# 05_-_USB.net
KiCad netlist of a schematic drawn in Altium Designer
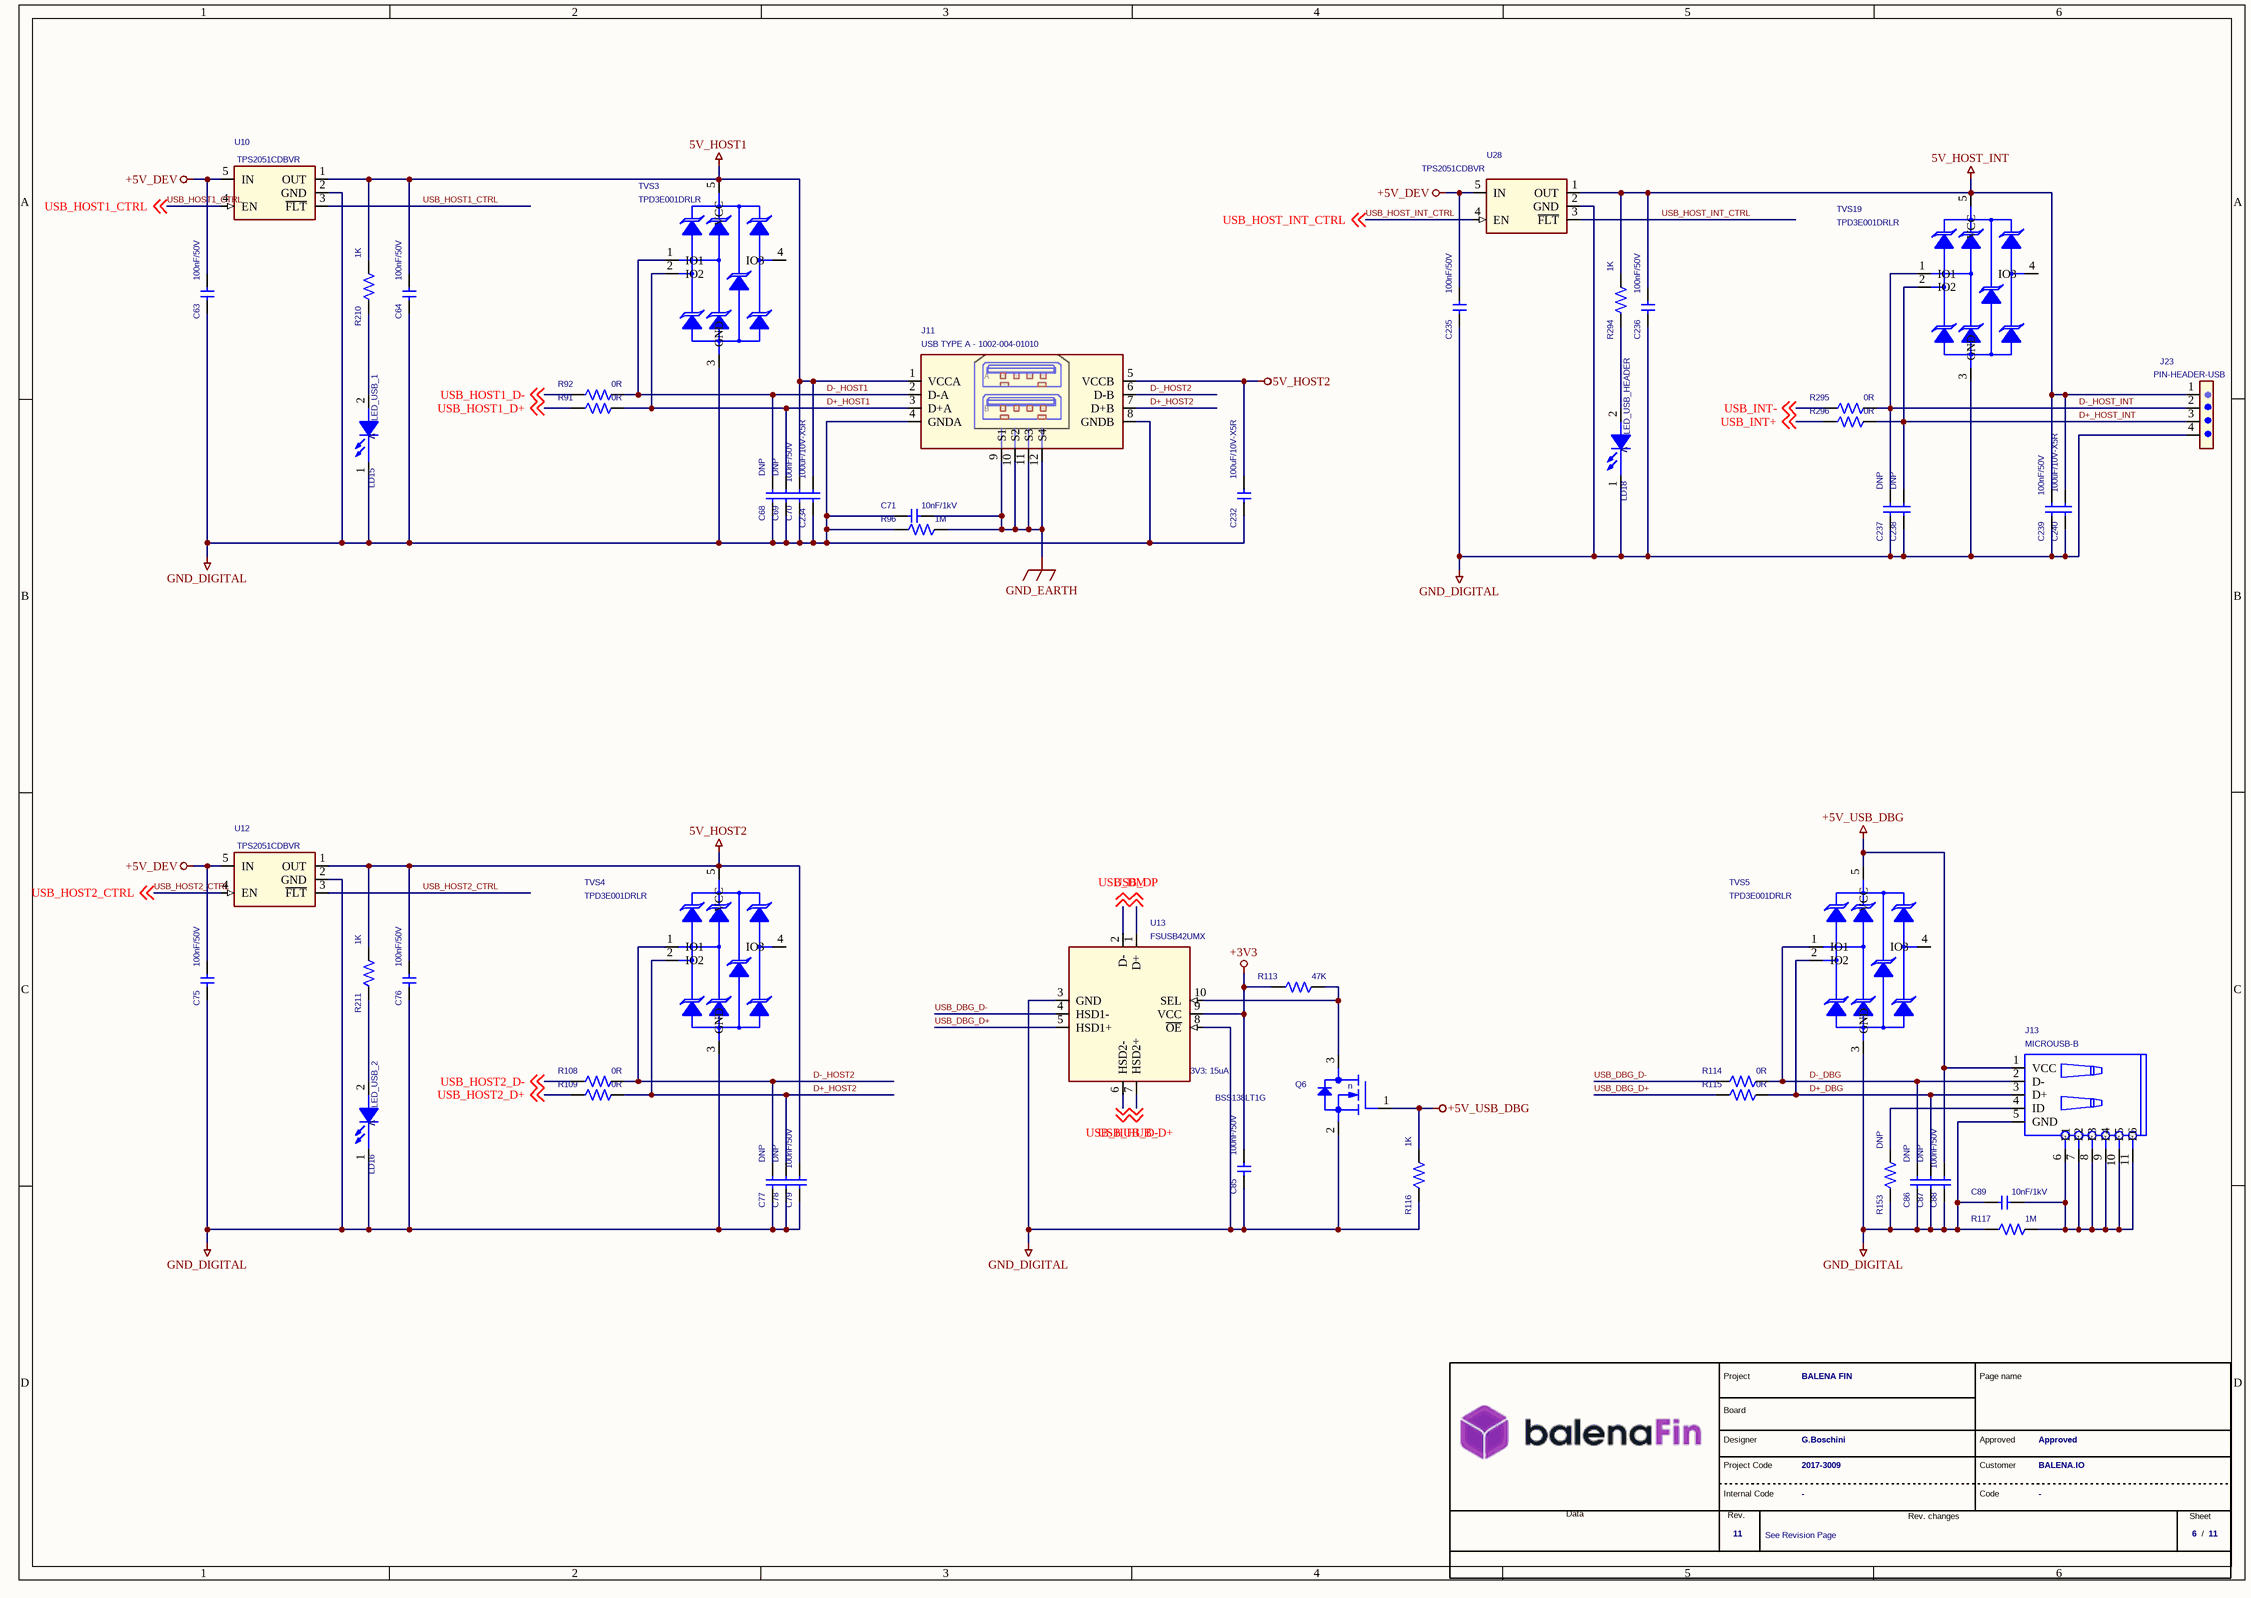
[diagram p0: 05 - USB.SchDoc]

(export (version "E")
  (design (tool "Eeschema 10.0.6"))
  (components
    (comp (ref "C63")
      (value "100nF/50V")
      (footprint "CS-C-0402")
      (description "CHIP CAP.CER. 100nF 16V 10% X7R 0402")
      (fields (field (name "MPN") "Generic"))
      (libsource (lib "*") (part "CS-C-0402-100n/16V"))
    )
    (comp (ref "C64")
      (value "100nF/50V")
      (footprint "CS-C-0402")
      (description "CHIP CAP.CER. 100nF 16V 10% X7R 0402")
      (fields (field (name "MPN") "Generic"))
      (libsource (lib "*") (part "CS-C-0402-100n/16V"))
    )
    (comp (ref "C68")
      (value "DNP")
      (footprint "CS-C-0402")
      (description "CHIP CAP.CER. 0402")
      (fields (field (name "MPN") "Generic"))
      (libsource (lib "*") (part "CS-C-0402"))
    )
    (comp (ref "C69")
      (value "DNP")
      (footprint "CS-C-0402")
      (description "CHIP CAP.CER. 0402")
      (fields (field (name "MPN") "Generic"))
      (libsource (lib "*") (part "CS-C-0402"))
    )
    (comp (ref "C70")
      (value "100nF/50V")
      (footprint "CS-C-0402")
      (description "CHIP CAP.CER. 100nF 16V 10% X7R 0402")
      (fields (field (name "MPN") "Generic"))
      (libsource (lib "*") (part "CS-C-0402-100n/16V"))
    )
    (comp (ref "C71")
      (value "10nF/1kV")
      (footprint "CS-C-1206")
      (description "CHIP CAP.CER. 10nF 1000V 10% X7R 1206")
      (fields (field (name "MPN") "Generic"))
      (libsource (lib "*") (part "CS-C-1206-10n/1kV"))
    )
    (comp (ref "C75")
      (value "100nF/50V")
      (footprint "CS-C-0402")
      (description "CHIP CAP.CER. 100nF 16V 10% X7R 0402")
      (fields (field (name "MPN") "Generic"))
      (libsource (lib "*") (part "CS-C-0402-100n/16V"))
    )
    (comp (ref "C76")
      (value "100nF/50V")
      (footprint "CS-C-0402")
      (description "CHIP CAP.CER. 100nF 16V 10% X7R 0402")
      (fields (field (name "MPN") "Generic"))
      (libsource (lib "*") (part "CS-C-0402-100n/16V"))
    )
    (comp (ref "C77")
      (value "DNP")
      (footprint "CS-C-0402")
      (description "CHIP CAP.CER. 0402")
      (fields (field (name "MPN") "Generic"))
      (libsource (lib "*") (part "CS-C-0402"))
    )
    (comp (ref "C78")
      (value "DNP")
      (footprint "CS-C-0402")
      (description "CHIP CAP.CER. 0402")
      (fields (field (name "MPN") "Generic"))
      (libsource (lib "*") (part "CS-C-0402"))
    )
    (comp (ref "C79")
      (value "100nF/50V")
      (footprint "CS-C-0402")
      (description "CHIP CAP.CER. 100nF 16V 10% X7R 0402")
      (fields (field (name "MPN") "Generic"))
      (libsource (lib "*") (part "CS-C-0402-100n/16V"))
    )
    (comp (ref "C85")
      (value "100nF/50V")
      (footprint "CS-C-0402")
      (description "CHIP CAP.CER. 100nF 16V 10% X7R 0402")
      (fields (field (name "MPN") "Generic"))
      (libsource (lib "*") (part "CS-C-0402-100n/16V"))
    )
    (comp (ref "C86")
      (value "DNP")
      (footprint "CS-C-0402")
      (description "CHIP CAP.CER. 0402")
      (fields (field (name "MPN") "Generic"))
      (libsource (lib "*") (part "CS-C-0402"))
    )
    (comp (ref "C87")
      (value "DNP")
      (footprint "CS-C-0402")
      (description "CHIP CAP.CER. 0402")
      (fields (field (name "MPN") "Generic"))
      (libsource (lib "*") (part "CS-C-0402"))
    )
    (comp (ref "C88")
      (value "100nF/50V")
      (footprint "CS-C-0402")
      (description "CHIP CAP.CER. 100nF 16V 10% X7R 0402")
      (fields (field (name "MPN") "Generic"))
      (libsource (lib "*") (part "CS-C-0402-100n/16V"))
    )
    (comp (ref "C89")
      (value "10nF/1kV")
      (footprint "CS-C-1206")
      (description "CHIP CAP.CER. 10nF 1000V 10% X7R 1206")
      (fields (field (name "MPN") "Generic"))
      (libsource (lib "*") (part "CS-C-1206-10n/1kV"))
    )
    (comp (ref "C232")
      (value "100uF/10V-X5R")
      (footprint "CS-C-1210")
      (description "CHIP CAP.CER. 100UF 10V 20% X5R 1210")
      (fields (field (name "MPN") "Generic"))
      (libsource (lib "*") (part "CS-C-1210-100u/10V-X5R"))
    )
    (comp (ref "C234")
      (value "100uF/10V-X5R")
      (footprint "CS-C-1210")
      (description "CHIP CAP.CER. 100UF 10V 20% X5R 1210")
      (fields (field (name "MPN") "Generic"))
      (libsource (lib "*") (part "CS-C-1210-100u/10V-X5R"))
    )
    (comp (ref "C235")
      (value "100nF/50V")
      (footprint "CS-C-0402")
      (description "CHIP CAP.CER. 100nF 16V 10% X7R 0402")
      (fields (field (name "MPN") "Generic"))
      (libsource (lib "*") (part "CS-C-0402-100n/16V"))
    )
    (comp (ref "C236")
      (value "100nF/50V")
      (footprint "CS-C-0402")
      (description "CHIP CAP.CER. 100nF 16V 10% X7R 0402")
      (fields (field (name "MPN") "Generic"))
      (libsource (lib "*") (part "CS-C-0402-100n/16V"))
    )
    (comp (ref "C237")
      (value "DNP")
      (footprint "CS-C-0402")
      (description "CHIP CAP.CER. 0402")
      (fields (field (name "MPN") "Generic"))
      (libsource (lib "*") (part "CS-C-0402"))
    )
    (comp (ref "C238")
      (value "DNP")
      (footprint "CS-C-0402")
      (description "CHIP CAP.CER. 0402")
      (fields (field (name "MPN") "Generic"))
      (libsource (lib "*") (part "CS-C-0402"))
    )
    (comp (ref "C239")
      (value "100nF/50V")
      (footprint "CS-C-0402")
      (description "CHIP CAP.CER. 100nF 16V 10% X7R 0402")
      (fields (field (name "MPN") "Generic"))
      (libsource (lib "*") (part "CS-C-0402-100n/16V"))
    )
    (comp (ref "C240")
      (value "100uF/10V-X5R")
      (footprint "CS-C-1210")
      (description "CHIP CAP.CER. 100UF 10V 20% X5R 1210")
      (fields (field (name "MPN") "Generic"))
      (libsource (lib "*") (part "CS-C-1210-100u/10V-X5R"))
    )
    (comp (ref "J11")
      (value "USB TYPE A - 1002-004-01010")
      (footprint "J-8-0200-FOT-USB-A-2X")
      (description "USB-A (USB TYPE-A), Stacked USB 2.0 Receptacle Connector 8 Position Through Hole, Right Angle")
      (fields (field (name "MPN") "1002-004-01010"))
      (libsource (lib "*") (part "USB - J-8-0200-FOT-USB-A-2X"))
    )
    (comp (ref "J13")
      (value "MICROUSB-B")
      (footprint "J-5-0065-FOS-MICROUSB10118192")
      (description "USB - micro B USB 2.0 Receptacle Connector 5 Position Surface Mount, Right Angle")
      (fields (field (name "MPN") "10118192-0001LF"))
      (libsource (lib "*") (part "USB - MICROUSB-B-FCI10118192"))
    )
    (comp (ref "J23")
      (value "PIN-HEADER-USB")
      (footprint "J-4-0254-MDT")
      (description "CONN HEADER THT 4POS 2.54MM SINGLE ROW")
      (fields (field (name "MPN") "Generic"))
      (libsource (lib "*") (part "STRIP-J-4-0254-MDT"))
    )
    (comp (ref "LD15")
      (value "LED_USB_1")
      (footprint "LD-0603")
      (description "LED Green 0603 SMT")
      (fields (field (name "MPN") "Generic"))
      (libsource (lib "*") (part "LED V - GENERICO - 0603"))
    )
    (comp (ref "LD16")
      (value "LED_USB_2")
      (footprint "LD-0603")
      (description "LED Green 0603 SMT")
      (fields (field (name "MPN") "Generic"))
      (libsource (lib "*") (part "LED V - GENERICO - 0603"))
    )
    (comp (ref "LD18")
      (value "LED_USB_HEADER")
      (footprint "LD-0603")
      (description "LED Green 0603 SMT")
      (fields (field (name "MPN") "Generic"))
      (libsource (lib "*") (part "LED V - GENERICO - 0603"))
    )
    (comp (ref "Q6")
      (value "BSS138LT1G")
      (footprint "SOT23")
      (description "MOSFET N-CH 50V 220MA SOT23-3")
      (libsource (lib "*") (part "NMOS - BSS138 - 0.2A/50V"))
    )
    (comp (ref "R91")
      (value "0R")
      (footprint "RS-0402")
      (description "CHIP RES. 0R 0402 1/16W 1%")
      (fields (field (name "MPN") "Generic"))
      (libsource (lib "*") (part "RS-0402-0r"))
    )
    (comp (ref "R92")
      (value "0R")
      (footprint "RS-0402")
      (description "CHIP RES. 0R 0402 1/16W 1%")
      (fields (field (name "MPN") "Generic"))
      (libsource (lib "*") (part "RS-0402-0r"))
    )
    (comp (ref "R96")
      (value "1M")
      (footprint "RS-1206")
      (description "CHIP RES. 1M 1206 1/4W 1%")
      (fields (field (name "MPN") "Generic"))
      (libsource (lib "*") (part "RS-1206-1M"))
    )
    (comp (ref "R108")
      (value "0R")
      (footprint "RS-0402")
      (description "CHIP RES. 0R 0402 1/16W 1%")
      (fields (field (name "MPN") "Generic"))
      (libsource (lib "*") (part "RS-0402-0r"))
    )
    (comp (ref "R109")
      (value "0R")
      (footprint "RS-0402")
      (description "CHIP RES. 0R 0402 1/16W 1%")
      (fields (field (name "MPN") "Generic"))
      (libsource (lib "*") (part "RS-0402-0r"))
    )
    (comp (ref "R113")
      (value "47K")
      (footprint "RS-0402")
      (description "CHIP RES. 47K 0402 1/16W 1% 100PPM/°C")
      (fields (field (name "MPN") "Generic"))
      (libsource (lib "*") (part "RS-0402-47k"))
    )
    (comp (ref "R114")
      (value "0R")
      (footprint "RS-0402")
      (description "CHIP RES. 0R 0402 1/16W 1%")
      (fields (field (name "MPN") "Generic"))
      (libsource (lib "*") (part "RS-0402-0r"))
    )
    (comp (ref "R115")
      (value "0R")
      (footprint "RS-0402")
      (description "CHIP RES. 0R 0402 1/16W 1%")
      (fields (field (name "MPN") "Generic"))
      (libsource (lib "*") (part "RS-0402-0r"))
    )
    (comp (ref "R116")
      (value "1K")
      (footprint "RS-0402")
      (description "CHIP RES. 1K 0402 1/16W 1%")
      (fields (field (name "MPN") "Generic"))
      (libsource (lib "*") (part "RS-0402-1k"))
    )
    (comp (ref "R117")
      (value "1M")
      (footprint "RS-1206")
      (description "CHIP RES. 1M 1206 1/4W 1%")
      (fields (field (name "MPN") "Generic"))
      (libsource (lib "*") (part "RS-1206-1M"))
    )
    (comp (ref "R153")
      (value "DNP")
      (footprint "RS-0402")
      (description "CHIP RES. 0402")
      (fields (field (name "MPN") "Generic"))
      (libsource (lib "*") (part "RS-0402"))
    )
    (comp (ref "R210")
      (value "1K")
      (footprint "RS-0402")
      (description "CHIP RES. 1K 0402 1/16W 1%")
      (fields (field (name "MPN") "Generic"))
      (libsource (lib "*") (part "RS-0402-1k"))
    )
    (comp (ref "R211")
      (value "1K")
      (footprint "RS-0402")
      (description "CHIP RES. 1K 0402 1/16W 1%")
      (fields (field (name "MPN") "Generic"))
      (libsource (lib "*") (part "RS-0402-1k"))
    )
    (comp (ref "R294")
      (value "1K")
      (footprint "RS-0402")
      (description "CHIP RES. 1K 0402 1/16W 1%")
      (fields (field (name "MPN") "Generic"))
      (libsource (lib "*") (part "RS-0402-1k"))
    )
    (comp (ref "R295")
      (value "0R")
      (footprint "RS-0402")
      (description "CHIP RES. 0R 0402 1/16W 1%")
      (fields (field (name "MPN") "Generic"))
      (libsource (lib "*") (part "RS-0402-0r"))
    )
    (comp (ref "R296")
      (value "0R")
      (footprint "RS-0402")
      (description "CHIP RES. 0R 0402 1/16W 1%")
      (fields (field (name "MPN") "Generic"))
      (libsource (lib "*") (part "RS-0402-0r"))
    )
    (comp (ref "TVS3")
      (value "TPD3E001DRLR")
      (footprint "SOP5_USON6")
      (description "TVS DIODE 5.5VWM")
      (libsource (lib "*") (part "TVS-UNI3x - TPD3E001DRLR - USB"))
    )
    (comp (ref "TVS4")
      (value "TPD3E001DRLR")
      (footprint "SOP5_USON6")
      (description "TVS DIODE 5.5VWM")
      (libsource (lib "*") (part "TVS-UNI3x - TPD3E001DRLR - USB"))
    )
    (comp (ref "TVS5")
      (value "TPD3E001DRLR")
      (footprint "SOP5_USON6")
      (description "TVS DIODE 5.5VWM")
      (libsource (lib "*") (part "TVS-UNI3x - TPD3E001DRLR - USB"))
    )
    (comp (ref "TVS19")
      (value "TPD3E001DRLR")
      (footprint "SOP5_USON6")
      (description "TVS DIODE 5.5VWM")
      (libsource (lib "*") (part "TVS-UNI3x - TPD3E001DRLR - USB"))
    )
    (comp (ref "U10")
      (value "TPS2051CDBVR")
      (footprint "SOT23-5")
      (description "Power Switch/Driver 1:1 N-Channel 500mA SOT-23-5")
      (libsource (lib "*") (part "USB-PSW - TPS2051CDBVR"))
    )
    (comp (ref "U12")
      (value "TPS2051CDBVR")
      (footprint "SOT23-5")
      (description "Power Switch/Driver 1:1 N-Channel 500mA SOT-23-5")
      (libsource (lib "*") (part "USB-PSW - TPS2051CDBVR"))
    )
    (comp (ref "U13")
      (value "FSUSB42UMX")
      (footprint "UMLP10")
      (description "USB Switch IC 1 Channel 10-UMLP (1.8x1.4)")
      (fields (field (name "POWER REQUIREMENTS") "3V3: 15uA"))
      (libsource (lib "*") (part "SWITCH-USB - FSUSB42UMX"))
    )
    (comp (ref "U28")
      (value "TPS2051CDBVR")
      (footprint "SOT23-5")
      (description "Power Switch/Driver 1:1 N-Channel 500mA SOT-23-5")
      (libsource (lib "*") (part "USB-PSW - TPS2051CDBVR"))
    )
  )
  (nets
    (net (code "1") (name "+3V3") (class "Default")
      (node (ref "C85") (pin "1") (pinfunction "1_1") (pintype "passive"))
      (node (ref "R113") (pin "1") (pinfunction "1_1") (pintype "passive"))
      (node (ref "U13") (pin "9") (pinfunction "VCC_9") (pintype "power_in"))
    )
    (net (code "2") (name "+5V_DEV") (class "Default")
      (node (ref "C235") (pin "1") (pinfunction "1_1") (pintype "passive"))
      (node (ref "C63") (pin "1") (pinfunction "1_1") (pintype "passive"))
      (node (ref "C75") (pin "1") (pinfunction "1_1") (pintype "passive"))
      (node (ref "U10") (pin "5") (pinfunction "IN_5") (pintype "power_in"))
      (node (ref "U12") (pin "5") (pinfunction "IN_5") (pintype "power_in"))
      (node (ref "U28") (pin "5") (pinfunction "IN_5") (pintype "power_in"))
    )
    (net (code "3") (name "+5V_USB_DBG") (class "Default")
      (node (ref "C88") (pin "1") (pinfunction "1_1") (pintype "passive"))
      (node (ref "J13") (pin "1") (pinfunction "VCC_1") (pintype "power_in"))
      (node (ref "Q6") (pin "1") (pinfunction "G_1") (pintype "passive"))
      (node (ref "R116") (pin "2") (pinfunction "2_2") (pintype "passive"))
      (node (ref "TVS5") (pin "5") (pinfunction "VCC_5") (pintype "passive"))
    )
    (net (code "4") (name "/D+_DBG") (class "Default")
      (node (ref "C87") (pin "1") (pinfunction "1_1") (pintype "passive"))
      (node (ref "J13") (pin "3") (pinfunction "D+_3") (pintype "bidirectional"))
      (node (ref "R115") (pin "2") (pinfunction "2_2") (pintype "passive"))
      (node (ref "TVS5") (pin "2") (pinfunction "IO2_2") (pintype "passive"))
    )
    (net (code "5") (name "/D+_HOST1") (class "Default")
      (node (ref "C69") (pin "1") (pinfunction "1_1") (pintype "passive"))
      (node (ref "J11") (pin "3") (pinfunction "D+A_3") (pintype "bidirectional"))
      (node (ref "R91") (pin "2") (pinfunction "2_2") (pintype "passive"))
      (node (ref "TVS3") (pin "2") (pinfunction "IO2_2") (pintype "passive"))
    )
    (net (code "6") (name "/D+_HOST2") (class "Default")
      (node (ref "C78") (pin "1") (pinfunction "1_1") (pintype "passive"))
      (node (ref "J11") (pin "7") (pinfunction "D+B_7") (pintype "bidirectional"))
      (node (ref "R109") (pin "2") (pinfunction "2_2") (pintype "passive"))
      (node (ref "TVS4") (pin "2") (pinfunction "IO2_2") (pintype "passive"))
    )
    (net (code "7") (name "/D+_HOST_INT") (class "Default")
      (node (ref "C238") (pin "1") (pinfunction "1_1") (pintype "passive"))
      (node (ref "J23") (pin "3") (pinfunction "3_3") (pintype "passive"))
      (node (ref "R296") (pin "2") (pinfunction "2_2") (pintype "passive"))
      (node (ref "TVS19") (pin "2") (pinfunction "IO2_2") (pintype "passive"))
    )
    (net (code "8") (name "/D-_DBG") (class "Default")
      (node (ref "C86") (pin "1") (pinfunction "1_1") (pintype "passive"))
      (node (ref "J13") (pin "2") (pinfunction "D-_2") (pintype "bidirectional"))
      (node (ref "R114") (pin "2") (pinfunction "2_2") (pintype "passive"))
      (node (ref "TVS5") (pin "1") (pinfunction "IO1_1") (pintype "passive"))
    )
    (net (code "9") (name "/D-_HOST1") (class "Default")
      (node (ref "C68") (pin "1") (pinfunction "1_1") (pintype "passive"))
      (node (ref "J11") (pin "2") (pinfunction "D-A_2") (pintype "bidirectional"))
      (node (ref "R92") (pin "2") (pinfunction "2_2") (pintype "passive"))
      (node (ref "TVS3") (pin "1") (pinfunction "IO1_1") (pintype "passive"))
    )
    (net (code "10") (name "/D-_HOST2") (class "Default")
      (node (ref "C77") (pin "1") (pinfunction "1_1") (pintype "passive"))
      (node (ref "J11") (pin "6") (pinfunction "D-B_6") (pintype "bidirectional"))
      (node (ref "R108") (pin "2") (pinfunction "2_2") (pintype "passive"))
      (node (ref "TVS4") (pin "1") (pinfunction "IO1_1") (pintype "passive"))
    )
    (net (code "11") (name "/D-_HOST_INT") (class "Default")
      (node (ref "C237") (pin "1") (pinfunction "1_1") (pintype "passive"))
      (node (ref "J23") (pin "2") (pinfunction "2_2") (pintype "passive"))
      (node (ref "R295") (pin "2") (pinfunction "2_2") (pintype "passive"))
      (node (ref "TVS19") (pin "1") (pinfunction "IO1_1") (pintype "passive"))
    )
    (net (code "12") (name "/USB_DBG_D+") (class "Default")
      (node (ref "R115") (pin "1") (pinfunction "1_1") (pintype "passive"))
      (node (ref "U13") (pin "5") (pinfunction "HSD1+_5") (pintype "bidirectional"))
    )
    (net (code "13") (name "/USB_DBG_D-") (class "Default")
      (node (ref "R114") (pin "1") (pinfunction "1_1") (pintype "passive"))
      (node (ref "U13") (pin "4") (pinfunction "HSD1-_4") (pintype "bidirectional"))
    )
    (net (code "14") (name "5V_HOST1") (class "Default")
      (node (ref "C234") (pin "1") (pinfunction "1_1") (pintype "passive"))
      (node (ref "C64") (pin "1") (pinfunction "1_1") (pintype "passive"))
      (node (ref "C70") (pin "1") (pinfunction "1_1") (pintype "passive"))
      (node (ref "J11") (pin "1") (pinfunction "VCCA_1") (pintype "power_in"))
      (node (ref "R210") (pin "2") (pinfunction "2_2") (pintype "passive"))
      (node (ref "TVS3") (pin "5") (pinfunction "VCC_5") (pintype "passive"))
      (node (ref "U10") (pin "1") (pinfunction "OUT_1") (pintype "power_in"))
    )
    (net (code "15") (name "5V_HOST2") (class "Default")
      (node (ref "C232") (pin "1") (pinfunction "1_1") (pintype "passive"))
      (node (ref "C76") (pin "1") (pinfunction "1_1") (pintype "passive"))
      (node (ref "C79") (pin "1") (pinfunction "1_1") (pintype "passive"))
      (node (ref "J11") (pin "5") (pinfunction "VCCB_5") (pintype "power_in"))
      (node (ref "R211") (pin "2") (pinfunction "2_2") (pintype "passive"))
      (node (ref "TVS4") (pin "5") (pinfunction "VCC_5") (pintype "passive"))
      (node (ref "U12") (pin "1") (pinfunction "OUT_1") (pintype "power_in"))
    )
    (net (code "16") (name "5V_HOST_INT") (class "Default")
      (node (ref "C236") (pin "1") (pinfunction "1_1") (pintype "passive"))
      (node (ref "C239") (pin "1") (pinfunction "1_1") (pintype "passive"))
      (node (ref "C240") (pin "1") (pinfunction "1_1") (pintype "passive"))
      (node (ref "J23") (pin "1") (pinfunction "1_1") (pintype "passive"))
      (node (ref "R294") (pin "2") (pinfunction "2_2") (pintype "passive"))
      (node (ref "TVS19") (pin "5") (pinfunction "VCC_5") (pintype "passive"))
      (node (ref "U28") (pin "1") (pinfunction "OUT_1") (pintype "power_in"))
    )
    (net (code "17") (name "GND_DIGITAL") (class "Default")
      (node (ref "C232") (pin "2") (pinfunction "2_2") (pintype "passive"))
      (node (ref "C234") (pin "2") (pinfunction "2_2") (pintype "passive"))
      (node (ref "C235") (pin "2") (pinfunction "2_2") (pintype "passive"))
      (node (ref "C236") (pin "2") (pinfunction "2_2") (pintype "passive"))
      (node (ref "C237") (pin "2") (pinfunction "2_2") (pintype "passive"))
      (node (ref "C238") (pin "2") (pinfunction "2_2") (pintype "passive"))
      (node (ref "C239") (pin "2") (pinfunction "2_2") (pintype "passive"))
      (node (ref "C240") (pin "2") (pinfunction "2_2") (pintype "passive"))
      (node (ref "C63") (pin "2") (pinfunction "2_2") (pintype "passive"))
      (node (ref "C64") (pin "2") (pinfunction "2_2") (pintype "passive"))
      (node (ref "C68") (pin "2") (pinfunction "2_2") (pintype "passive"))
      (node (ref "C69") (pin "2") (pinfunction "2_2") (pintype "passive"))
      (node (ref "C70") (pin "2") (pinfunction "2_2") (pintype "passive"))
      (node (ref "C71") (pin "1") (pinfunction "1_1") (pintype "passive"))
      (node (ref "C75") (pin "2") (pinfunction "2_2") (pintype "passive"))
      (node (ref "C76") (pin "2") (pinfunction "2_2") (pintype "passive"))
      (node (ref "C77") (pin "2") (pinfunction "2_2") (pintype "passive"))
      (node (ref "C78") (pin "2") (pinfunction "2_2") (pintype "passive"))
      (node (ref "C79") (pin "2") (pinfunction "2_2") (pintype "passive"))
      (node (ref "C85") (pin "2") (pinfunction "2_2") (pintype "passive"))
      (node (ref "C86") (pin "2") (pinfunction "2_2") (pintype "passive"))
      (node (ref "C87") (pin "2") (pinfunction "2_2") (pintype "passive"))
      (node (ref "C88") (pin "2") (pinfunction "2_2") (pintype "passive"))
      (node (ref "C89") (pin "1") (pinfunction "1_1") (pintype "passive"))
      (node (ref "J11") (pin "4") (pinfunction "GNDA_4") (pintype "power_in"))
      (node (ref "J11") (pin "8") (pinfunction "GNDB_8") (pintype "power_in"))
      (node (ref "J13") (pin "5") (pinfunction "GND_5") (pintype "power_in"))
      (node (ref "J23") (pin "4") (pinfunction "4_4") (pintype "passive"))
      (node (ref "LD15") (pin "1") (pinfunction "C_1") (pintype "passive"))
      (node (ref "LD16") (pin "1") (pinfunction "C_1") (pintype "passive"))
      (node (ref "LD18") (pin "1") (pinfunction "C_1") (pintype "passive"))
      (node (ref "Q6") (pin "2") (pinfunction "S_2") (pintype "passive"))
      (node (ref "R116") (pin "1") (pinfunction "1_1") (pintype "passive"))
      (node (ref "R117") (pin "1") (pinfunction "1_1") (pintype "passive"))
      (node (ref "R153") (pin "1") (pinfunction "1_1") (pintype "passive"))
      (node (ref "R96") (pin "1") (pinfunction "1_1") (pintype "passive"))
      (node (ref "TVS19") (pin "3") (pinfunction "GND_3") (pintype "power_in"))
      (node (ref "TVS3") (pin "3") (pinfunction "GND_3") (pintype "power_in"))
      (node (ref "TVS4") (pin "3") (pinfunction "GND_3") (pintype "power_in"))
      (node (ref "TVS5") (pin "3") (pinfunction "GND_3") (pintype "power_in"))
      (node (ref "U10") (pin "2") (pinfunction "GND_2") (pintype "power_in"))
      (node (ref "U12") (pin "2") (pinfunction "GND_2") (pintype "power_in"))
      (node (ref "U13") (pin "3") (pinfunction "GND_3") (pintype "power_in"))
      (node (ref "U13") (pin "8") (pinfunction "~{OE}_8") (pintype "input"))
      (node (ref "U28") (pin "2") (pinfunction "GND_2") (pintype "power_in"))
    )
    (net (code "18") (name "GND_EARTH") (class "Default")
      (node (ref "C71") (pin "2") (pinfunction "2_2") (pintype "passive"))
      (node (ref "J11") (pin "10") (pinfunction "S2_10") (pintype "passive"))
      (node (ref "J11") (pin "11") (pinfunction "S3_11") (pintype "passive"))
      (node (ref "J11") (pin "12") (pinfunction "S4_12") (pintype "passive"))
      (node (ref "J11") (pin "9") (pinfunction "S1_9") (pintype "passive"))
      (node (ref "R96") (pin "2") (pinfunction "2_2") (pintype "passive"))
    )
    (net (code "19") (name "Net-(J13-E1)") (class "Default")
      (node (ref "C89") (pin "2") (pinfunction "2_2") (pintype "passive"))
      (node (ref "J13") (pin "10") (pinfunction "E5_10") (pintype "passive"))
      (node (ref "J13") (pin "11") (pinfunction "E6_11") (pintype "passive"))
      (node (ref "J13") (pin "6") (pinfunction "E1_6") (pintype "passive"))
      (node (ref "J13") (pin "7") (pinfunction "E2_7") (pintype "passive"))
      (node (ref "J13") (pin "8") (pinfunction "E3_8") (pintype "passive"))
      (node (ref "J13") (pin "9") (pinfunction "E4_9") (pintype "passive"))
      (node (ref "R117") (pin "2") (pinfunction "2_2") (pintype "passive"))
    )
    (net (code "20") (name "Net-(J13-ID)") (class "Default")
      (node (ref "J13") (pin "4") (pinfunction "ID_4") (pintype "passive"))
      (node (ref "R153") (pin "2") (pinfunction "2_2") (pintype "passive"))
    )
    (net (code "21") (name "Net-(LD15-A)") (class "Default")
      (node (ref "LD15") (pin "2") (pinfunction "A_2") (pintype "passive"))
      (node (ref "R210") (pin "1") (pinfunction "1_1") (pintype "passive"))
    )
    (net (code "22") (name "Net-(LD16-A)") (class "Default")
      (node (ref "LD16") (pin "2") (pinfunction "A_2") (pintype "passive"))
      (node (ref "R211") (pin "1") (pinfunction "1_1") (pintype "passive"))
    )
    (net (code "23") (name "Net-(LD18-A)") (class "Default")
      (node (ref "LD18") (pin "2") (pinfunction "A_2") (pintype "passive"))
      (node (ref "R294") (pin "1") (pinfunction "1_1") (pintype "passive"))
    )
    (net (code "24") (name "Net-(Q6-D)") (class "Default")
      (node (ref "Q6") (pin "3") (pinfunction "D_3") (pintype "passive"))
      (node (ref "R113") (pin "2") (pinfunction "2_2") (pintype "passive"))
      (node (ref "U13") (pin "10") (pinfunction "SEL_10") (pintype "input"))
    )
    (net (code "25") (name "USB_DM") (class "Default")
      (node (ref "U13") (pin "2") (pinfunction "D-_2") (pintype "bidirectional"))
    )
    (net (code "26") (name "USB_DP") (class "Default")
      (node (ref "U13") (pin "1") (pinfunction "D+_1") (pintype "bidirectional"))
    )
    (net (code "27") (name "USB_HOST1_CTRL") (class "Default")
      (node (ref "U10") (pin "3") (pinfunction "~{FLT}_3") (pintype "open_collector"))
      (node (ref "U10") (pin "4") (pinfunction "EN_4") (pintype "input"))
    )
    (net (code "28") (name "USB_HOST1_D+") (class "Default")
      (node (ref "R91") (pin "1") (pinfunction "1_1") (pintype "passive"))
    )
    (net (code "29") (name "USB_HOST1_D-") (class "Default")
      (node (ref "R92") (pin "1") (pinfunction "1_1") (pintype "passive"))
    )
    (net (code "30") (name "USB_HOST2_CTRL") (class "Default")
      (node (ref "U12") (pin "3") (pinfunction "~{FLT}_3") (pintype "open_collector"))
      (node (ref "U12") (pin "4") (pinfunction "EN_4") (pintype "input"))
    )
    (net (code "31") (name "USB_HOST2_D+") (class "Default")
      (node (ref "R109") (pin "1") (pinfunction "1_1") (pintype "passive"))
    )
    (net (code "32") (name "USB_HOST2_D-") (class "Default")
      (node (ref "R108") (pin "1") (pinfunction "1_1") (pintype "passive"))
    )
    (net (code "33") (name "USB_HOST_INT_CTRL") (class "Default")
      (node (ref "U28") (pin "3") (pinfunction "~{FLT}_3") (pintype "open_collector"))
      (node (ref "U28") (pin "4") (pinfunction "EN_4") (pintype "input"))
    )
    (net (code "34") (name "USB_HUB_D+") (class "Default")
      (node (ref "U13") (pin "7") (pinfunction "HSD2+_7") (pintype "bidirectional"))
    )
    (net (code "35") (name "USB_HUB_D-") (class "Default")
      (node (ref "U13") (pin "6") (pinfunction "HSD2-_6") (pintype "bidirectional"))
    )
    (net (code "36") (name "USB_INT+") (class "Default")
      (node (ref "R296") (pin "1") (pinfunction "1_1") (pintype "passive"))
    )
    (net (code "37") (name "USB_INT-") (class "Default")
      (node (ref "R295") (pin "1") (pinfunction "1_1") (pintype "passive"))
    )
    (net (code "38") (name "unconnected-(TVS3-IO3-Pad4)") (class "Default")
      (node (ref "TVS3") (pin "4") (pinfunction "IO3_4") (pintype "passive"))
    )
    (net (code "39") (name "unconnected-(TVS4-IO3-Pad4)") (class "Default")
      (node (ref "TVS4") (pin "4") (pinfunction "IO3_4") (pintype "passive"))
    )
    (net (code "40") (name "unconnected-(TVS5-IO3-Pad4)") (class "Default")
      (node (ref "TVS5") (pin "4") (pinfunction "IO3_4") (pintype "passive"))
    )
    (net (code "41") (name "unconnected-(TVS19-IO3-Pad4)") (class "Default")
      (node (ref "TVS19") (pin "4") (pinfunction "IO3_4") (pintype "passive"))
    )
  )
)
